# 5VAC-DCReg.net
KiCad netlist of a schematic drawn in EAGLE
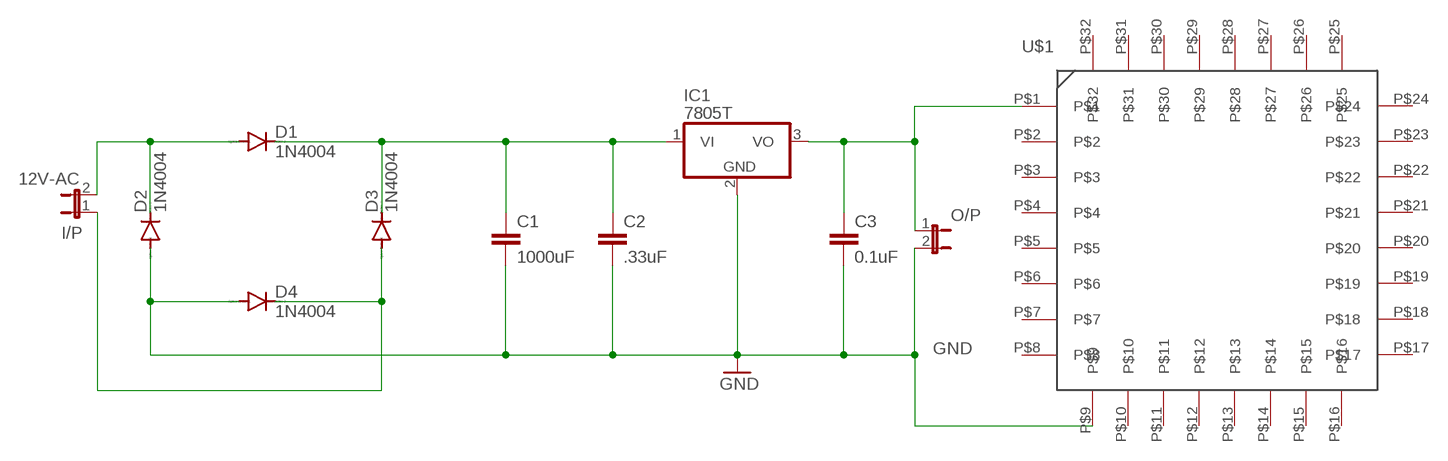
[diagram p0: schematic, sheet 1]

(export (version "E")
  (design (tool "Eeschema 10.0.6"))
  (components
    (comp (ref "C1")
      (value "1000uF")
      (footprint "eagle-import:C2.5-3")
      (libsource (lib "eagle-import") (part "C2,5-3"))
    )
    (comp (ref "C2")
      (value ".33uF")
      (footprint "eagle-import:C2.5-3")
      (libsource (lib "eagle-import") (part "C2,5-3"))
    )
    (comp (ref "C3")
      (value "0.1uF")
      (footprint "eagle-import:C2.5-3")
      (libsource (lib "eagle-import") (part "C2,5-3"))
    )
    (comp (ref "D1")
      (value "1N4004")
      (footprint "eagle-import:DO41-10")
      (libsource (lib "eagle-import") (part "1N4004"))
    )
    (comp (ref "D2")
      (value "1N4004")
      (footprint "eagle-import:DO41-10")
      (libsource (lib "eagle-import") (part "1N4004"))
    )
    (comp (ref "D3")
      (value "1N4004")
      (footprint "eagle-import:DO41-10")
      (libsource (lib "eagle-import") (part "1N4004"))
    )
    (comp (ref "D4")
      (value "1N4004")
      (footprint "eagle-import:DO41-10")
      (libsource (lib "eagle-import") (part "1N4004"))
    )
    (comp (ref "I/P")
      (value "12V-AC")
      (footprint "eagle-import:JP1")
      (libsource (lib "eagle-import") (part "JP1E"))
    )
    (comp (ref "IC1")
      (value "7805T")
      (footprint "eagle-import:TO220H")
      (libsource (lib "eagle-import") (part "78T05"))
    )
    (comp (ref "O/P")
      (value "JP1E")
      (footprint "eagle-import:JP1")
      (libsource (lib "eagle-import") (part "JP1E"))
    )
    (comp (ref "U$1")
      (value "MEGA8L-DEV")
      (footprint "eagle-import:TQFP-MEGA8L")
      (libsource (lib "eagle-import") (part "MEGA8L-DEV"))
    )
  )
  (nets
    (net (code "1") (name "GND") (class "Default")
      (node (ref "C1") (pin "2") (pinfunction "2_2") (pintype "passive"))
      (node (ref "C2") (pin "2") (pinfunction "2_2") (pintype "passive"))
      (node (ref "C3") (pin "2") (pinfunction "2_2") (pintype "passive"))
      (node (ref "D2") (pin "A") (pinfunction "A_A") (pintype "passive"))
      (node (ref "D4") (pin "A") (pinfunction "A_A") (pintype "passive"))
      (node (ref "IC1") (pin "2") (pinfunction "GND_2") (pintype "passive"))
      (node (ref "O/P") (pin "2") (pinfunction "2_2") (pintype "passive"))
      (node (ref "U$1") (pin "P$9") (pinfunction "P$9_P$9") (pintype "bidirectional"))
    )
    (net (code "2") (name "Net-(D1-PadA)") (class "Default")
      (node (ref "D1") (pin "A") (pinfunction "A_A") (pintype "passive"))
      (node (ref "D2") (pin "C") (pinfunction "C_C") (pintype "passive"))
      (node (ref "I/P") (pin "2") (pinfunction "2_2") (pintype "passive"))
    )
    (net (code "3") (name "Net-(D3-PadA)") (class "Default")
      (node (ref "D3") (pin "A") (pinfunction "A_A") (pintype "passive"))
      (node (ref "D4") (pin "C") (pinfunction "C_C") (pintype "passive"))
      (node (ref "I/P") (pin "1") (pinfunction "1_1") (pintype "passive"))
    )
    (net (code "4") (name "Net-(IC1-VI)") (class "Default")
      (node (ref "C1") (pin "1") (pinfunction "1_1") (pintype "passive"))
      (node (ref "C2") (pin "1") (pinfunction "1_1") (pintype "passive"))
      (node (ref "D1") (pin "C") (pinfunction "C_C") (pintype "passive"))
      (node (ref "D3") (pin "C") (pinfunction "C_C") (pintype "passive"))
      (node (ref "IC1") (pin "1") (pinfunction "VI_1") (pintype "input"))
    )
    (net (code "5") (name "Net-(IC1-VO)") (class "Default")
      (node (ref "C3") (pin "1") (pinfunction "1_1") (pintype "passive"))
      (node (ref "IC1") (pin "3") (pinfunction "VO_3") (pintype "passive"))
      (node (ref "O/P") (pin "1") (pinfunction "1_1") (pintype "passive"))
      (node (ref "U$1") (pin "P$1") (pinfunction "P$1_P$1") (pintype "bidirectional"))
    )
    (net (code "6") (name "unconnected-(U$1-PadP$2)") (class "Default")
      (node (ref "U$1") (pin "P$2") (pinfunction "P$2_P$2") (pintype "bidirectional"))
    )
    (net (code "7") (name "unconnected-(U$1-PadP$3)") (class "Default")
      (node (ref "U$1") (pin "P$3") (pinfunction "P$3_P$3") (pintype "bidirectional"))
    )
    (net (code "8") (name "unconnected-(U$1-PadP$4)") (class "Default")
      (node (ref "U$1") (pin "P$4") (pinfunction "P$4_P$4") (pintype "bidirectional"))
    )
    (net (code "9") (name "unconnected-(U$1-PadP$5)") (class "Default")
      (node (ref "U$1") (pin "P$5") (pinfunction "P$5_P$5") (pintype "bidirectional"))
    )
    (net (code "10") (name "unconnected-(U$1-PadP$6)") (class "Default")
      (node (ref "U$1") (pin "P$6") (pinfunction "P$6_P$6") (pintype "bidirectional"))
    )
    (net (code "11") (name "unconnected-(U$1-PadP$7)") (class "Default")
      (node (ref "U$1") (pin "P$7") (pinfunction "P$7_P$7") (pintype "bidirectional"))
    )
    (net (code "12") (name "unconnected-(U$1-PadP$8)") (class "Default")
      (node (ref "U$1") (pin "P$8") (pinfunction "P$8_P$8") (pintype "bidirectional"))
    )
    (net (code "13") (name "unconnected-(U$1-PadP$10)") (class "Default")
      (node (ref "U$1") (pin "P$10") (pinfunction "P$10_P$10") (pintype "bidirectional"))
    )
    (net (code "14") (name "unconnected-(U$1-PadP$11)") (class "Default")
      (node (ref "U$1") (pin "P$11") (pinfunction "P$11_P$11") (pintype "bidirectional"))
    )
    (net (code "15") (name "unconnected-(U$1-PadP$12)") (class "Default")
      (node (ref "U$1") (pin "P$12") (pinfunction "P$12_P$12") (pintype "bidirectional"))
    )
    (net (code "16") (name "unconnected-(U$1-PadP$13)") (class "Default")
      (node (ref "U$1") (pin "P$13") (pinfunction "P$13_P$13") (pintype "bidirectional"))
    )
    (net (code "17") (name "unconnected-(U$1-PadP$14)") (class "Default")
      (node (ref "U$1") (pin "P$14") (pinfunction "P$14_P$14") (pintype "bidirectional"))
    )
    (net (code "18") (name "unconnected-(U$1-PadP$15)") (class "Default")
      (node (ref "U$1") (pin "P$15") (pinfunction "P$15_P$15") (pintype "bidirectional"))
    )
    (net (code "19") (name "unconnected-(U$1-PadP$16)") (class "Default")
      (node (ref "U$1") (pin "P$16") (pinfunction "P$16_P$16") (pintype "bidirectional"))
    )
    (net (code "20") (name "unconnected-(U$1-PadP$17)") (class "Default")
      (node (ref "U$1") (pin "P$17") (pinfunction "P$17_P$17") (pintype "bidirectional"))
    )
    (net (code "21") (name "unconnected-(U$1-PadP$18)") (class "Default")
      (node (ref "U$1") (pin "P$18") (pinfunction "P$18_P$18") (pintype "bidirectional"))
    )
    (net (code "22") (name "unconnected-(U$1-PadP$19)") (class "Default")
      (node (ref "U$1") (pin "P$19") (pinfunction "P$19_P$19") (pintype "bidirectional"))
    )
    (net (code "23") (name "unconnected-(U$1-PadP$20)") (class "Default")
      (node (ref "U$1") (pin "P$20") (pinfunction "P$20_P$20") (pintype "bidirectional"))
    )
    (net (code "24") (name "unconnected-(U$1-PadP$21)") (class "Default")
      (node (ref "U$1") (pin "P$21") (pinfunction "P$21_P$21") (pintype "bidirectional"))
    )
    (net (code "25") (name "unconnected-(U$1-PadP$22)") (class "Default")
      (node (ref "U$1") (pin "P$22") (pinfunction "P$22_P$22") (pintype "bidirectional"))
    )
    (net (code "26") (name "unconnected-(U$1-PadP$23)") (class "Default")
      (node (ref "U$1") (pin "P$23") (pinfunction "P$23_P$23") (pintype "bidirectional"))
    )
    (net (code "27") (name "unconnected-(U$1-PadP$24)") (class "Default")
      (node (ref "U$1") (pin "P$24") (pinfunction "P$24_P$24") (pintype "bidirectional"))
    )
    (net (code "28") (name "unconnected-(U$1-PadP$25)") (class "Default")
      (node (ref "U$1") (pin "P$25") (pinfunction "P$25_P$25") (pintype "bidirectional"))
    )
    (net (code "29") (name "unconnected-(U$1-PadP$26)") (class "Default")
      (node (ref "U$1") (pin "P$26") (pinfunction "P$26_P$26") (pintype "bidirectional"))
    )
    (net (code "30") (name "unconnected-(U$1-PadP$27)") (class "Default")
      (node (ref "U$1") (pin "P$27") (pinfunction "P$27_P$27") (pintype "bidirectional"))
    )
    (net (code "31") (name "unconnected-(U$1-PadP$28)") (class "Default")
      (node (ref "U$1") (pin "P$28") (pinfunction "P$28_P$28") (pintype "bidirectional"))
    )
    (net (code "32") (name "unconnected-(U$1-PadP$29)") (class "Default")
      (node (ref "U$1") (pin "P$29") (pinfunction "P$29_P$29") (pintype "bidirectional"))
    )
    (net (code "33") (name "unconnected-(U$1-PadP$30)") (class "Default")
      (node (ref "U$1") (pin "P$30") (pinfunction "P$30_P$30") (pintype "bidirectional"))
    )
    (net (code "34") (name "unconnected-(U$1-PadP$31)") (class "Default")
      (node (ref "U$1") (pin "P$31") (pinfunction "P$31_P$31") (pintype "bidirectional"))
    )
    (net (code "35") (name "unconnected-(U$1-PadP$32)") (class "Default")
      (node (ref "U$1") (pin "P$32") (pinfunction "P$32_P$32") (pintype "bidirectional"))
    )
  )
)
